# DM1092_Power_Supply.net
KiCad netlist of a schematic drawn in Altium Designer
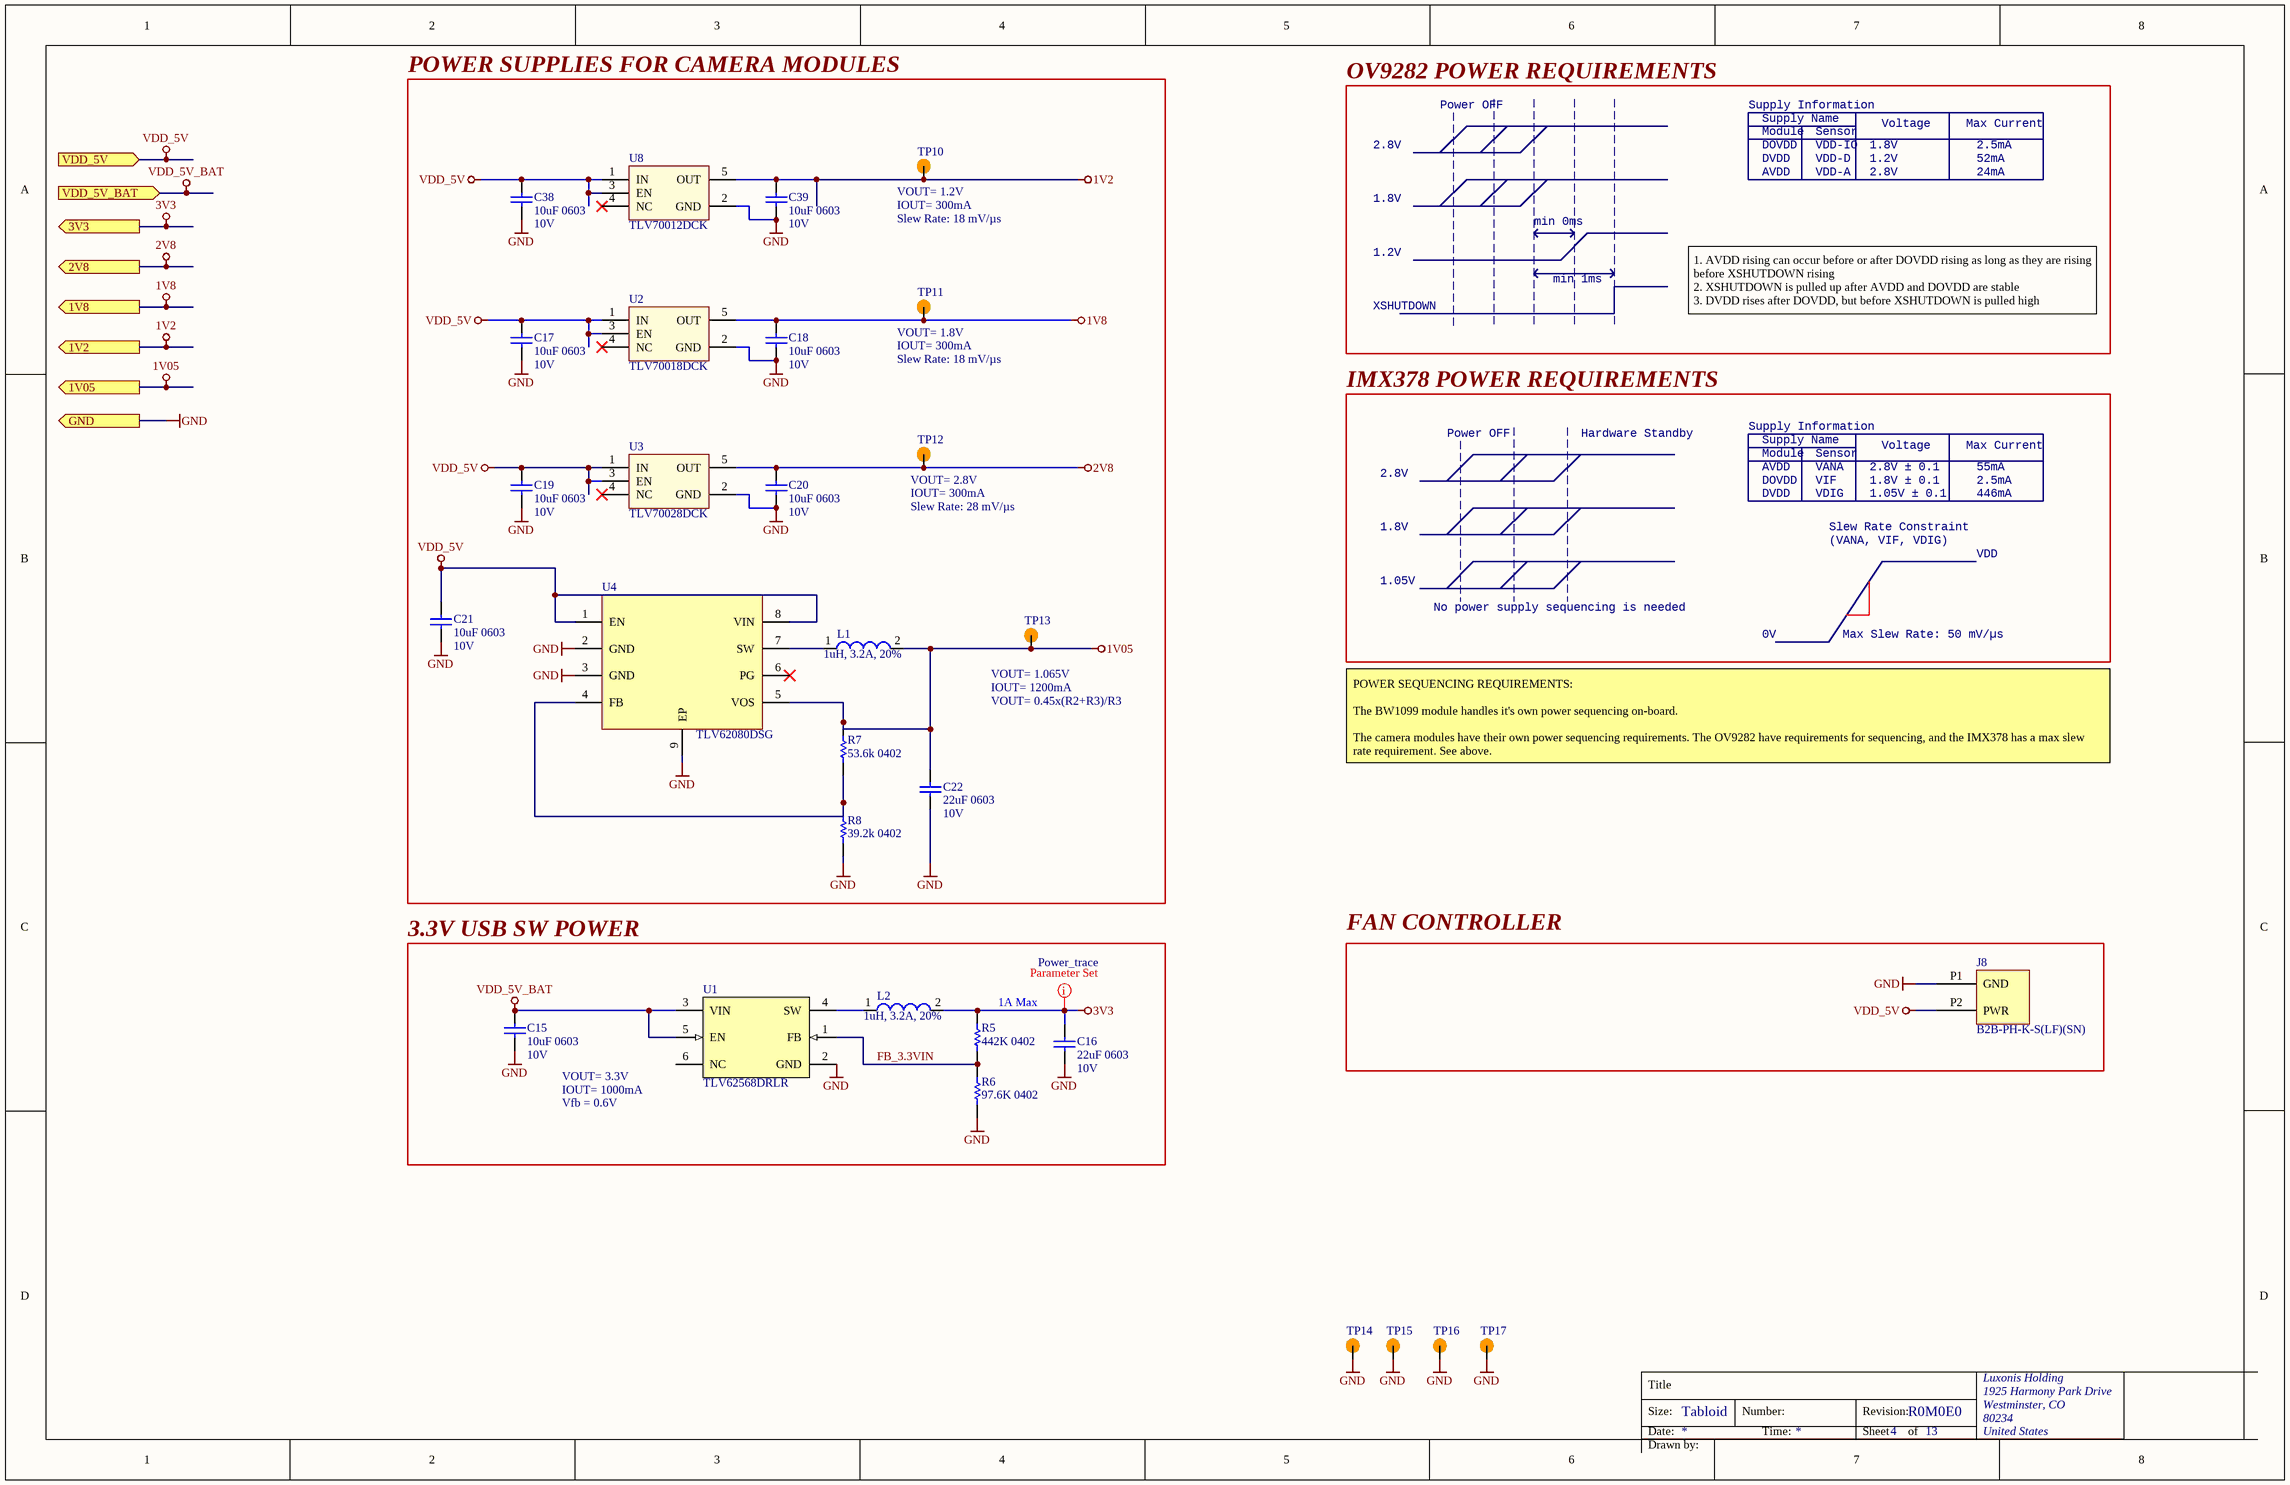
[diagram p0: DM1092_Power_Supply.SchDoc]

(export (version "E")
  (design (tool "Eeschema 10.0.6"))
  (components
    (comp (ref "C15")
      (value "10uF 0603")
      (footprint "CAP_Altium_Vault_Generic:CAPC0603(1608)100_L")
      (description "CAP CER 10UF 10V X5R 0603 20%")
      (fields (field (name "TOLERANCE") "20%") (field (name "VOLTAGE RATING") "10V"))
      (libsource (lib "LuxonisMaster") (part "GRM188R61A106ME69D"))
    )
    (comp (ref "C16")
      (value "22uF 0603")
      (footprint "CAP_Altium_Vault_Generic:CAPC0603(1608)100_N")
      (description "CAP CER 22UF 10V X5R 0603 20%")
      (fields (field (name "TOLERANCE") "20%") (field (name "VOLTAGE RATING") "10V"))
      (libsource (lib "LuxonisMaster") (part "GRM188R61A226ME15D"))
    )
    (comp (ref "C17")
      (value "10uF 0603")
      (footprint "CAP_Altium_Vault_Generic:CAPC0603(1608)100_L")
      (description "CAP CER 10UF 10V X5R 0603 20%")
      (fields (field (name "TOLERANCE") "20%") (field (name "VOLTAGE RATING") "10V"))
      (libsource (lib "LuxonisMaster") (part "GRM188R61A106ME69D"))
    )
    (comp (ref "C18")
      (value "10uF 0603")
      (footprint "CAP_Altium_Vault_Generic:CAPC0603(1608)100_L")
      (description "CAP CER 10UF 10V X5R 0603 20%")
      (fields (field (name "TOLERANCE") "20%") (field (name "VOLTAGE RATING") "10V"))
      (libsource (lib "LuxonisMaster") (part "GRM188R61A106ME69D"))
    )
    (comp (ref "C19")
      (value "10uF 0603")
      (footprint "CAP_Altium_Vault_Generic:CAPC0603(1608)100_L")
      (description "CAP CER 10UF 10V X5R 0603 20%")
      (fields (field (name "TOLERANCE") "20%") (field (name "VOLTAGE RATING") "10V"))
      (libsource (lib "LuxonisMaster") (part "GRM188R61A106ME69D"))
    )
    (comp (ref "C20")
      (value "10uF 0603")
      (footprint "CAP_Altium_Vault_Generic:CAPC0603(1608)100_L")
      (description "CAP CER 10UF 10V X5R 0603 20%")
      (fields (field (name "TOLERANCE") "20%") (field (name "VOLTAGE RATING") "10V"))
      (libsource (lib "LuxonisMaster") (part "GRM188R61A106ME69D"))
    )
    (comp (ref "C21")
      (value "10uF 0603")
      (footprint "CAP_Altium_Vault_Generic:CAPC0603(1608)100_L")
      (description "CAP CER 10UF 10V X5R 0603 20%")
      (fields (field (name "TOLERANCE") "20%") (field (name "VOLTAGE RATING") "10V"))
      (libsource (lib "LuxonisMaster") (part "GRM188R61A106ME69D"))
    )
    (comp (ref "C22")
      (value "22uF 0603")
      (footprint "CAP_Altium_Vault_Generic:CAPC0603(1608)100_L")
      (description "CAP CER 22UF 10V X5R 0603 20%")
      (fields (field (name "TOLERANCE") "20%") (field (name "VOLTAGE RATING") "10V"))
      (libsource (lib "LuxonisMaster") (part "GRM188R61A226ME15D"))
    )
    (comp (ref "C38")
      (value "10uF 0603")
      (footprint "CAP_Altium_Vault_Generic:CAPC0603(1608)100_L")
      (description "CAP CER 10UF 10V X5R 0603 20%")
      (fields (field (name "TOLERANCE") "20%") (field (name "VOLTAGE RATING") "10V"))
      (libsource (lib "LuxonisMaster") (part "GRM188R61A106ME69D"))
    )
    (comp (ref "C39")
      (value "10uF 0603")
      (footprint "CAP_Altium_Vault_Generic:CAPC0603(1608)100_L")
      (description "CAP CER 10UF 10V X5R 0603 20%")
      (fields (field (name "TOLERANCE") "20%") (field (name "VOLTAGE RATING") "10V"))
      (libsource (lib "LuxonisMaster") (part "GRM188R61A106ME69D"))
    )
    (comp (ref "J8")
      (value "B2B-PH-K-S(LF)(SN)")
      (footprint "LuxonisMaster:B2B-PH-K-S(LF)(SN)")
      (description "CONN HEADER VERT 2POS 2MM")
      (libsource (lib "LuxonisMaster") (part "B2B-PH-K-S(LF)(SN)"))
    )
    (comp (ref "L1")
      (value "1uH, 3.2A, 20%")
      (footprint "LuxonisMaster:DFE252012P-1R0M=P2")
      (description "FIXED IND 1UH 3.2A 42 MOHM SMD")
      (fields (field (name "MANUFACTURER PART NUMBER") "DFE252012P-1R0M=P2") (field (name "TOLERANCE") "20%"))
      (libsource (lib "LuxonisMaster") (part "DFE252012P-1R0M=P2"))
    )
    (comp (ref "L2")
      (value "1uH, 3.2A, 20%")
      (footprint "LuxonisMaster:DFE252012P-1R0M=P2")
      (description "FIXED IND 1UH 3.2A 42 MOHM SMD")
      (fields (field (name "MANUFACTURER PART NUMBER") "DFE252012P-1R0M=P2") (field (name "TOLERANCE") "20%"))
      (libsource (lib "LuxonisMaster") (part "DFE252012P-1R0M=P2"))
    )
    (comp (ref "R5")
      (value "442K 0402")
      (footprint "RESC0402(1005)_N")
      (description "RES SMD 442K OHM 1% 1/16W 0402")
      (fields (field (name "TOLERANCE") "1%"))
      (libsource (lib "DM1092_R0M0E0") (part "CRCW0402442KFKED"))
    )
    (comp (ref "R6")
      (value "97.6K 0402")
      (footprint "RESC0402(1005)_N")
      (description "RES SMD 97.6K OHM 1% 1/16W 0402")
      (fields (field (name "TOLERANCE") "1%"))
      (libsource (lib "DM1092_R0M0E0") (part "CRCW040297K6FKED"))
    )
    (comp (ref "R7")
      (value "53.6k 0402")
      (footprint "RES_Altium_Vault_Generic:RESC0402(1005)_L")
      (description "RES SMD 53.6K OHM 1% 1/16W 0402")
      (fields (field (name "TOLERANCE") "1%"))
      (libsource (lib "LuxonisMaster") (part "CRCW040253K6FKED"))
    )
    (comp (ref "R8")
      (value "39.2k 0402")
      (footprint "RES_Altium_Vault_Generic:RESC0402(1005)_L")
      (description "RES SMD 39.2K OHM 1% 1/16W 0402")
      (fields (field (name "TOLERANCE") "1%"))
      (libsource (lib "LuxonisMaster") (part "CRCW040239K2FKED"))
    )
    (comp (ref "TP10")
      (value "TP100_200_NS")
      (footprint "LuxonisMaster:TP100_200_NS")
      (libsource (lib "LuxonisMaster") (part "TEST_POINT"))
    )
    (comp (ref "TP11")
      (value "TP100_200_NS")
      (footprint "LuxonisMaster:TP100_200_NS")
      (libsource (lib "LuxonisMaster") (part "TEST_POINT"))
    )
    (comp (ref "TP12")
      (value "TP100_200_NS")
      (footprint "LuxonisMaster:TP100_200_NS")
      (libsource (lib "LuxonisMaster") (part "TEST_POINT"))
    )
    (comp (ref "TP13")
      (value "TP100_200_NS")
      (footprint "LuxonisMaster:TP100_200_NS")
      (libsource (lib "LuxonisMaster") (part "TEST_POINT"))
    )
    (comp (ref "TP14")
      (value "TP100_200_NS")
      (footprint "LuxonisMaster:TP100_200_NS")
      (libsource (lib "LuxonisMaster") (part "TEST_POINT"))
    )
    (comp (ref "TP15")
      (value "TP100_200_NS")
      (footprint "LuxonisMaster:TP100_200_NS")
      (libsource (lib "LuxonisMaster") (part "TEST_POINT"))
    )
    (comp (ref "TP16")
      (value "TP100_200_NS")
      (footprint "LuxonisMaster:TP100_200_NS")
      (libsource (lib "LuxonisMaster") (part "TEST_POINT"))
    )
    (comp (ref "TP17")
      (value "TP100_200_NS")
      (footprint "LuxonisMaster:TP100_200_NS")
      (libsource (lib "LuxonisMaster") (part "TEST_POINT"))
    )
    (comp (ref "U1")
      (value "TLV62568DRLR")
      (footprint "TLV62568DRLR")
      (description "IC REG BUCK ADJ 1A SOT563-6")
      (libsource (lib "DM1092_R0M0E0") (part "TLV62568DRLR"))
    )
    (comp (ref "U2")
      (value "TLV70018DCK")
      (footprint "LuxonisMaster:TLV70018DCK")
      (description "IC REG LINEAR 1.8V 200MA SC70-5 Linear Voltage Regulator IC  1 Output  200mA SC-70-5")
      (libsource (lib "LuxonisMaster") (part "TLV70018DCK"))
    )
    (comp (ref "U3")
      (value "TLV70028DCK")
      (footprint "LuxonisMaster:TLV70028DCK")
      (description "IC REG LINEAR 2.8V 200MA SC70-5 Linear Voltage Regulator IC  1 Output  200mA SC-70-5")
      (libsource (lib "LuxonisMaster") (part "TLV70028DCK"))
    )
    (comp (ref "U4")
      (value "TLV62080DSG")
      (footprint "LuxonisMaster:TLV62080DSG")
      (description "IC REG BUCK ADJ 1.2A SYNC 8WSON")
      (libsource (lib "LuxonisMaster") (part "TLV62080DSG"))
    )
    (comp (ref "U8")
      (value "TLV70012DCK")
      (footprint "LuxonisMaster:TLV70012DCK")
      (description "IC REG LINEAR 1.2V 200MA SC70-5")
      (libsource (lib "LuxonisMaster") (part "TLV70012DCK"))
    )
  )
  (nets
    (net (code "1") (name "/FB_3.3VIN") (class "Default")
      (node (ref "R5") (pin "1") (pinfunction "1_1") (pintype "passive"))
      (node (ref "R6") (pin "2") (pinfunction "2_2") (pintype "passive"))
      (node (ref "U1") (pin "1") (pinfunction "FB_1") (pintype "input"))
    )
    (net (code "2") (name "1V2") (class "Default")
      (node (ref "C39") (pin "2") (pinfunction "2_2") (pintype "passive"))
      (node (ref "TP10") (pin "1") (pintype "passive"))
      (node (ref "U8") (pin "5") (pinfunction "OUT_5") (pintype "passive"))
    )
    (net (code "3") (name "1V05") (class "Default")
      (node (ref "C22") (pin "2") (pinfunction "2_2") (pintype "passive"))
      (node (ref "L1") (pin "2") (pinfunction "2_2") (pintype "passive"))
      (node (ref "R7") (pin "2") (pinfunction "2_2") (pintype "passive"))
      (node (ref "TP13") (pin "1") (pintype "passive"))
      (node (ref "U4") (pin "5") (pinfunction "VOS_5") (pintype "passive"))
    )
    (net (code "4") (name "1V8") (class "Default")
      (node (ref "C18") (pin "2") (pinfunction "2_2") (pintype "passive"))
      (node (ref "TP11") (pin "1") (pintype "passive"))
      (node (ref "U2") (pin "5") (pinfunction "OUT_5") (pintype "passive"))
    )
    (net (code "5") (name "2V8") (class "Default")
      (node (ref "C20") (pin "2") (pinfunction "2_2") (pintype "passive"))
      (node (ref "TP12") (pin "1") (pintype "passive"))
      (node (ref "U3") (pin "5") (pinfunction "OUT_5") (pintype "passive"))
    )
    (net (code "6") (name "3V3") (class "Default")
      (node (ref "C16") (pin "1") (pinfunction "1_1") (pintype "passive"))
      (node (ref "L2") (pin "2") (pinfunction "2_2") (pintype "passive"))
      (node (ref "R5") (pin "2") (pinfunction "2_2") (pintype "passive"))
    )
    (net (code "7") (name "GND") (class "Default")
      (node (ref "C15") (pin "1") (pinfunction "1_1") (pintype "passive"))
      (node (ref "C16") (pin "2") (pinfunction "2_2") (pintype "passive"))
      (node (ref "C17") (pin "1") (pinfunction "1_1") (pintype "passive"))
      (node (ref "C18") (pin "1") (pinfunction "1_1") (pintype "passive"))
      (node (ref "C19") (pin "1") (pinfunction "1_1") (pintype "passive"))
      (node (ref "C20") (pin "1") (pinfunction "1_1") (pintype "passive"))
      (node (ref "C21") (pin "1") (pinfunction "1_1") (pintype "passive"))
      (node (ref "C22") (pin "1") (pinfunction "1_1") (pintype "passive"))
      (node (ref "C38") (pin "1") (pinfunction "1_1") (pintype "passive"))
      (node (ref "C39") (pin "1") (pinfunction "1_1") (pintype "passive"))
      (node (ref "J8") (pin "P1") (pinfunction "GND_P1") (pintype "passive"))
      (node (ref "R6") (pin "1") (pinfunction "1_1") (pintype "passive"))
      (node (ref "R8") (pin "1") (pinfunction "1_1") (pintype "passive"))
      (node (ref "TP14") (pin "1") (pintype "passive"))
      (node (ref "TP15") (pin "1") (pintype "passive"))
      (node (ref "TP16") (pin "1") (pintype "passive"))
      (node (ref "TP17") (pin "1") (pintype "passive"))
      (node (ref "U1") (pin "2") (pinfunction "GND_2") (pintype "power_in"))
      (node (ref "U2") (pin "2") (pinfunction "GND_2") (pintype "passive"))
      (node (ref "U3") (pin "2") (pinfunction "GND_2") (pintype "passive"))
      (node (ref "U4") (pin "2") (pinfunction "GND_2") (pintype "passive"))
      (node (ref "U4") (pin "3") (pinfunction "GND_3") (pintype "passive"))
      (node (ref "U4") (pin "9") (pinfunction "EP_9") (pintype "passive"))
      (node (ref "U8") (pin "2") (pinfunction "GND_2") (pintype "passive"))
    )
    (net (code "8") (name "Net-(U1-SW)") (class "Default")
      (node (ref "L2") (pin "1") (pinfunction "1_1") (pintype "passive"))
      (node (ref "U1") (pin "4") (pinfunction "SW_4") (pintype "power_in"))
    )
    (net (code "9") (name "Net-(U4-FB)") (class "Default")
      (node (ref "R7") (pin "1") (pinfunction "1_1") (pintype "passive"))
      (node (ref "R8") (pin "2") (pinfunction "2_2") (pintype "passive"))
      (node (ref "U4") (pin "4") (pinfunction "FB_4") (pintype "passive"))
    )
    (net (code "10") (name "Net-(U4-SW)") (class "Default")
      (node (ref "L1") (pin "1") (pinfunction "1_1") (pintype "passive"))
      (node (ref "U4") (pin "7") (pinfunction "SW_7") (pintype "passive"))
    )
    (net (code "11") (name "VDD_5V") (class "Default")
      (node (ref "C17") (pin "2") (pinfunction "2_2") (pintype "passive"))
      (node (ref "C19") (pin "2") (pinfunction "2_2") (pintype "passive"))
      (node (ref "C21") (pin "2") (pinfunction "2_2") (pintype "passive"))
      (node (ref "C38") (pin "2") (pinfunction "2_2") (pintype "passive"))
      (node (ref "J8") (pin "P2") (pinfunction "PWR_P2") (pintype "passive"))
      (node (ref "U2") (pin "1") (pinfunction "IN_1") (pintype "passive"))
      (node (ref "U2") (pin "3") (pinfunction "EN_3") (pintype "passive"))
      (node (ref "U3") (pin "1") (pinfunction "IN_1") (pintype "passive"))
      (node (ref "U3") (pin "3") (pinfunction "EN_3") (pintype "passive"))
      (node (ref "U4") (pin "1") (pinfunction "EN_1") (pintype "passive"))
      (node (ref "U4") (pin "8") (pinfunction "VIN_8") (pintype "passive"))
      (node (ref "U8") (pin "1") (pinfunction "IN_1") (pintype "passive"))
      (node (ref "U8") (pin "3") (pinfunction "EN_3") (pintype "passive"))
    )
    (net (code "12") (name "VDD_5V_BAT") (class "Default")
      (node (ref "C15") (pin "2") (pinfunction "2_2") (pintype "passive"))
      (node (ref "U1") (pin "3") (pinfunction "VIN_3") (pintype "power_in"))
      (node (ref "U1") (pin "5") (pinfunction "EN_5") (pintype "input"))
    )
    (net (code "13") (name "unconnected-(U1-NC-Pad6)") (class "Default")
      (node (ref "U1") (pin "6") (pinfunction "NC_6") (pintype "passive"))
    )
    (net (code "14") (name "unconnected-(U2-NC-Pad4)") (class "Default")
      (node (ref "U2") (pin "4") (pinfunction "NC_4") (pintype "passive+no_connect"))
    )
    (net (code "15") (name "unconnected-(U3-NC-Pad4)") (class "Default")
      (node (ref "U3") (pin "4") (pinfunction "NC_4") (pintype "passive+no_connect"))
    )
    (net (code "16") (name "unconnected-(U4-PG-Pad6)") (class "Default")
      (node (ref "U4") (pin "6") (pinfunction "PG_6") (pintype "passive+no_connect"))
    )
    (net (code "17") (name "unconnected-(U8-NC-Pad4)") (class "Default")
      (node (ref "U8") (pin "4") (pinfunction "NC_4") (pintype "passive+no_connect"))
    )
  )
)
